# NRF24-SHIM.net
KiCad netlist of a schematic drawn in EAGLE
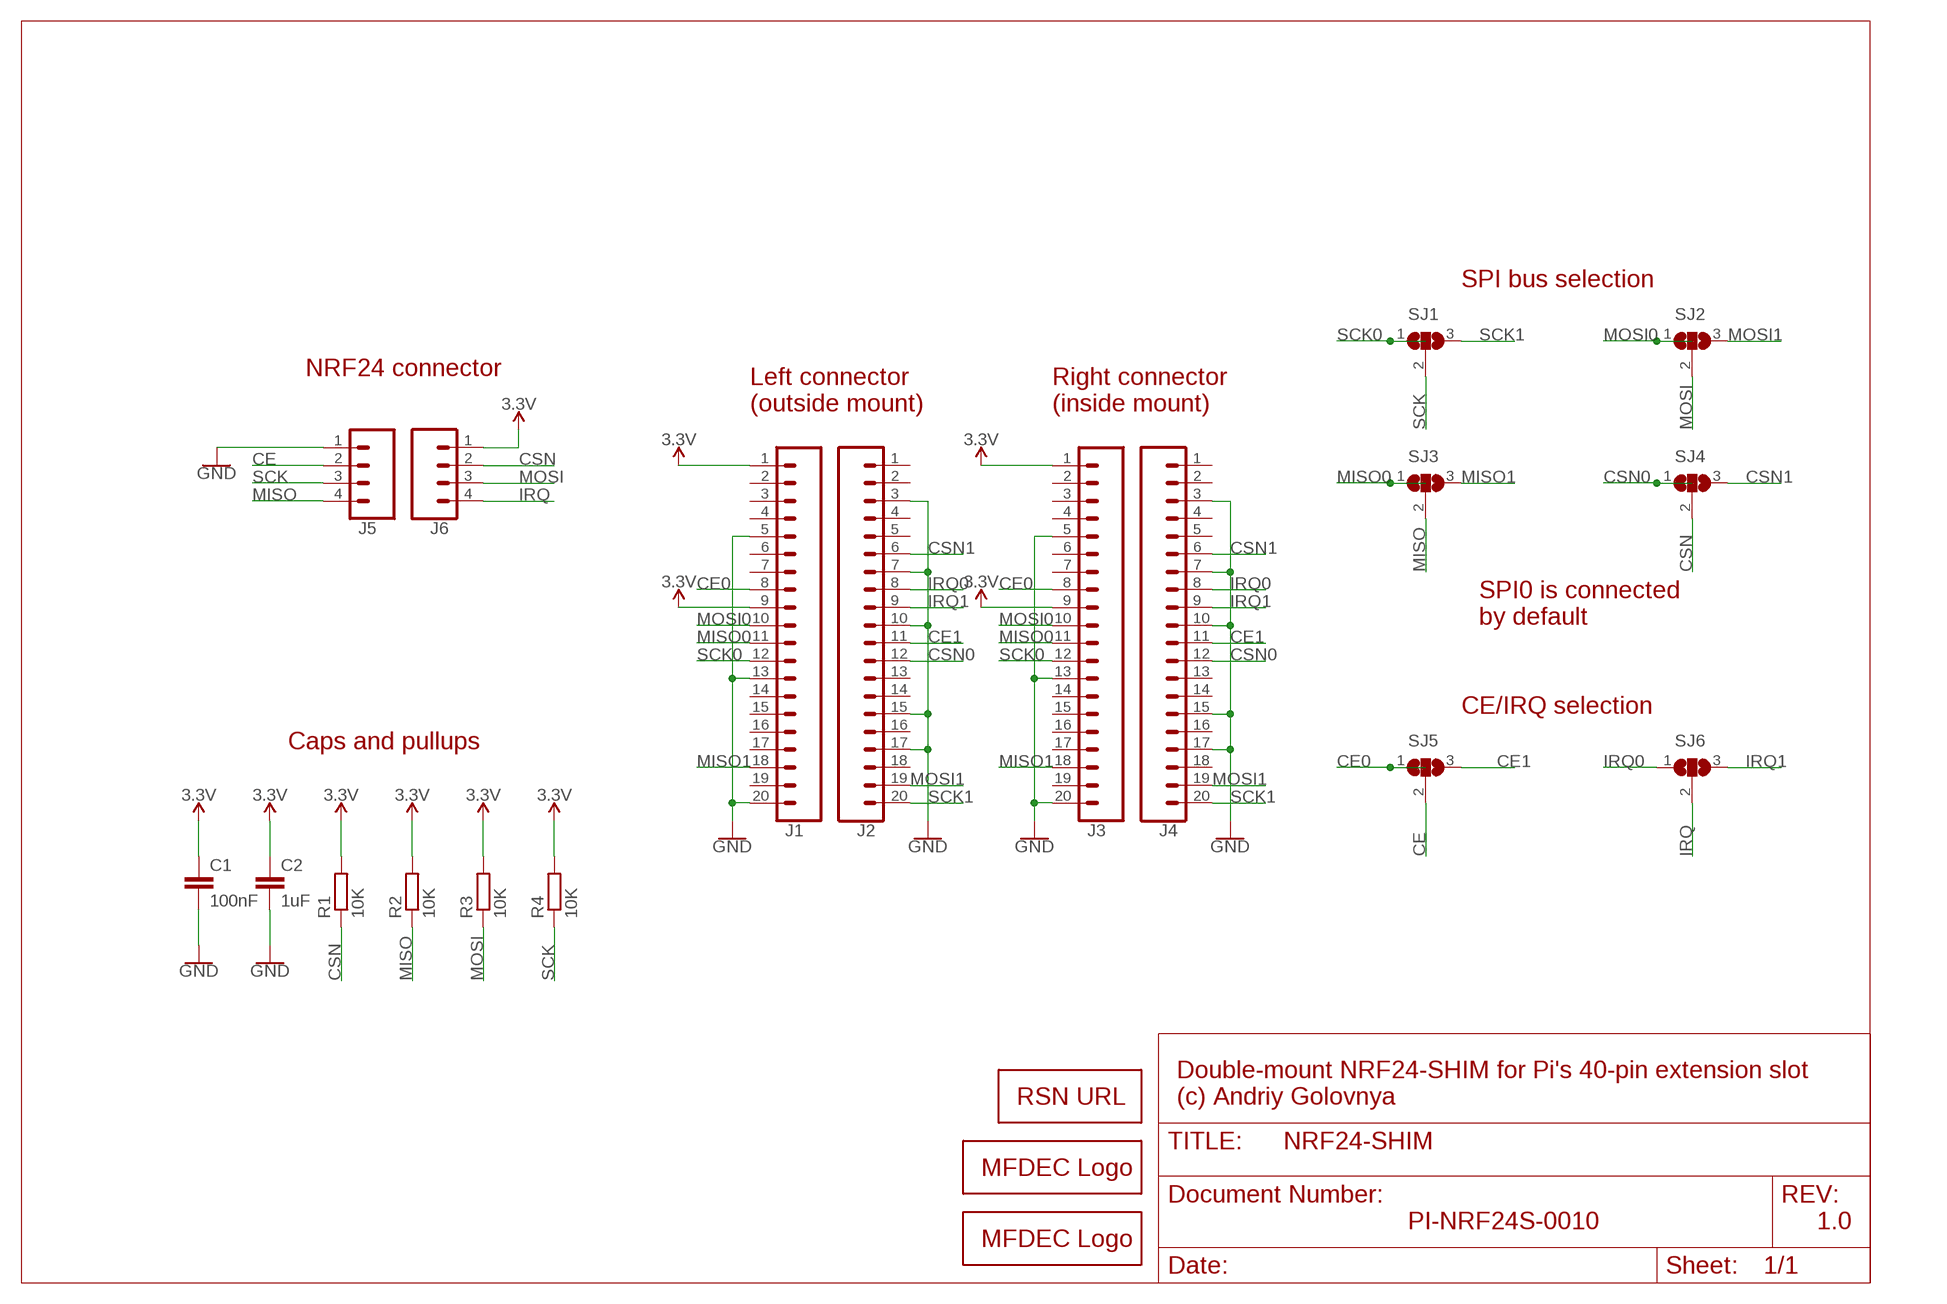
[diagram p0: schematic, sheet 1]

(export (version "E")
  (design (tool "Eeschema 10.0.6"))
  (components
    (comp (ref "C1")
      (value "100nF")
      (footprint "eagle-import:C0402")
      (libsource (lib "eagle-import") (part "C-EUC0402"))
    )
    (comp (ref "C2")
      (value "1uF")
      (footprint "eagle-import:C0603")
      (libsource (lib "eagle-import") (part "C-EUC0603"))
    )
    (comp (ref "J1")
      (value "CONN_20LOCK")
      (footprint "eagle-import:1X20_LOCK")
      (libsource (lib "eagle-import") (part "CONN_20LOCK"))
    )
    (comp (ref "J2")
      (value "CONN_20LOCK")
      (footprint "eagle-import:1X20_LOCK")
      (libsource (lib "eagle-import") (part "CONN_20LOCK"))
    )
    (comp (ref "J3")
      (value "CONN_20LOCK")
      (footprint "eagle-import:1X20_LOCK")
      (libsource (lib "eagle-import") (part "CONN_20LOCK"))
    )
    (comp (ref "J4")
      (value "CONN_20LOCK")
      (footprint "eagle-import:1X20_LOCK")
      (libsource (lib "eagle-import") (part "CONN_20LOCK"))
    )
    (comp (ref "J5")
      (value "CONN_04LOCK")
      (footprint "eagle-import:1X04_LOCK")
      (libsource (lib "eagle-import") (part "CONN_04LOCK"))
    )
    (comp (ref "J6")
      (value "CONN_04LOCK")
      (footprint "eagle-import:1X04_LOCK")
      (libsource (lib "eagle-import") (part "CONN_04LOCK"))
    )
    (comp (ref "LOGO1")
      (value "MFDECLOGO_SQ_8MM")
      (footprint "eagle-import:MFDEC_SQ_8MM")
      (libsource (lib "eagle-import") (part "MFDECLOGO_SQ_8MM"))
    )
    (comp (ref "LOGO2")
      (value "MFDECLOGO_L_20MM")
      (footprint "eagle-import:MFDEC_L_20MM")
      (libsource (lib "eagle-import") (part "MFDECLOGO_L_20MM"))
    )
    (comp (ref "LOGO3")
      (value "RSNURL_QR_10MM")
      (footprint "eagle-import:RSNURL_QR_10MM")
      (libsource (lib "eagle-import") (part "RSNURL_QR_10MM"))
    )
    (comp (ref "R1")
      (value "10K")
      (footprint "eagle-import:R0402")
      (libsource (lib "eagle-import") (part "R-EU_R0402"))
    )
    (comp (ref "R2")
      (value "10K")
      (footprint "eagle-import:R0402")
      (libsource (lib "eagle-import") (part "R-EU_R0402"))
    )
    (comp (ref "R3")
      (value "10K")
      (footprint "eagle-import:R0402")
      (libsource (lib "eagle-import") (part "R-EU_R0402"))
    )
    (comp (ref "R4")
      (value "10K")
      (footprint "eagle-import:R0402")
      (libsource (lib "eagle-import") (part "R-EU_R0402"))
    )
    (comp (ref "SJ1")
      (value "SJ2")
      (footprint "eagle-import:SJ_2")
      (libsource (lib "eagle-import") (part "SJ2"))
    )
    (comp (ref "SJ2")
      (value "SJ2")
      (footprint "eagle-import:SJ_2")
      (libsource (lib "eagle-import") (part "SJ2"))
    )
    (comp (ref "SJ3")
      (value "SJ2")
      (footprint "eagle-import:SJ_2")
      (libsource (lib "eagle-import") (part "SJ2"))
    )
    (comp (ref "SJ4")
      (value "SJ2")
      (footprint "eagle-import:SJ_2")
      (libsource (lib "eagle-import") (part "SJ2"))
    )
    (comp (ref "SJ5")
      (value "SJ2")
      (footprint "eagle-import:SJ_2")
      (libsource (lib "eagle-import") (part "SJ2"))
    )
    (comp (ref "SJ6")
      (value "SJ2")
      (footprint "eagle-import:SJ_2")
      (libsource (lib "eagle-import") (part "SJ2"))
    )
  )
  (nets
    (net (code "1") (name "/CE") (class "Default")
      (node (ref "J5") (pin "2") (pinfunction "2_2") (pintype "passive"))
      (node (ref "SJ5") (pin "2") (pinfunction "2_2") (pintype "passive"))
    )
    (net (code "2") (name "/CE0") (class "Default")
      (node (ref "J1") (pin "8") (pinfunction "8_8") (pintype "passive"))
      (node (ref "J3") (pin "8") (pinfunction "8_8") (pintype "passive"))
      (node (ref "SJ5") (pin "1") (pinfunction "1_1") (pintype "passive"))
    )
    (net (code "3") (name "/CE1") (class "Default")
      (node (ref "J2") (pin "11") (pinfunction "11_11") (pintype "passive"))
      (node (ref "J4") (pin "11") (pinfunction "11_11") (pintype "passive"))
      (node (ref "SJ5") (pin "3") (pinfunction "3_3") (pintype "passive"))
    )
    (net (code "4") (name "/CSN") (class "Default")
      (node (ref "J6") (pin "2") (pinfunction "2_2") (pintype "passive"))
      (node (ref "R1") (pin "1") (pinfunction "1_1") (pintype "passive"))
      (node (ref "SJ4") (pin "2") (pinfunction "2_2") (pintype "passive"))
    )
    (net (code "5") (name "/CSN0") (class "Default")
      (node (ref "J2") (pin "12") (pinfunction "12_12") (pintype "passive"))
      (node (ref "J4") (pin "12") (pinfunction "12_12") (pintype "passive"))
      (node (ref "SJ4") (pin "1") (pinfunction "1_1") (pintype "passive"))
    )
    (net (code "6") (name "/CSN1") (class "Default")
      (node (ref "J2") (pin "6") (pinfunction "6_6") (pintype "passive"))
      (node (ref "J4") (pin "6") (pinfunction "6_6") (pintype "passive"))
      (node (ref "SJ4") (pin "3") (pinfunction "3_3") (pintype "passive"))
    )
    (net (code "7") (name "/IRQ") (class "Default")
      (node (ref "J6") (pin "4") (pinfunction "4_4") (pintype "passive"))
      (node (ref "SJ6") (pin "2") (pinfunction "2_2") (pintype "passive"))
    )
    (net (code "8") (name "/IRQ0") (class "Default")
      (node (ref "J2") (pin "8") (pinfunction "8_8") (pintype "passive"))
      (node (ref "J4") (pin "8") (pinfunction "8_8") (pintype "passive"))
      (node (ref "SJ6") (pin "1") (pinfunction "1_1") (pintype "passive"))
    )
    (net (code "9") (name "/IRQ1") (class "Default")
      (node (ref "J2") (pin "9") (pinfunction "9_9") (pintype "passive"))
      (node (ref "J4") (pin "9") (pinfunction "9_9") (pintype "passive"))
      (node (ref "SJ6") (pin "3") (pinfunction "3_3") (pintype "passive"))
    )
    (net (code "10") (name "/MISO") (class "Default")
      (node (ref "J5") (pin "4") (pinfunction "4_4") (pintype "passive"))
      (node (ref "R2") (pin "1") (pinfunction "1_1") (pintype "passive"))
      (node (ref "SJ3") (pin "2") (pinfunction "2_2") (pintype "passive"))
    )
    (net (code "11") (name "/MISO0") (class "Default")
      (node (ref "J1") (pin "11") (pinfunction "11_11") (pintype "passive"))
      (node (ref "J3") (pin "11") (pinfunction "11_11") (pintype "passive"))
      (node (ref "SJ3") (pin "1") (pinfunction "1_1") (pintype "passive"))
    )
    (net (code "12") (name "/MISO1") (class "Default")
      (node (ref "J1") (pin "18") (pinfunction "18_18") (pintype "passive"))
      (node (ref "J3") (pin "18") (pinfunction "18_18") (pintype "passive"))
      (node (ref "SJ3") (pin "3") (pinfunction "3_3") (pintype "passive"))
    )
    (net (code "13") (name "/MOSI") (class "Default")
      (node (ref "J6") (pin "3") (pinfunction "3_3") (pintype "passive"))
      (node (ref "R3") (pin "1") (pinfunction "1_1") (pintype "passive"))
      (node (ref "SJ2") (pin "2") (pinfunction "2_2") (pintype "passive"))
    )
    (net (code "14") (name "/MOSI0") (class "Default")
      (node (ref "J1") (pin "10") (pinfunction "10_10") (pintype "passive"))
      (node (ref "J3") (pin "10") (pinfunction "10_10") (pintype "passive"))
      (node (ref "SJ2") (pin "1") (pinfunction "1_1") (pintype "passive"))
    )
    (net (code "15") (name "/MOSI1") (class "Default")
      (node (ref "J2") (pin "19") (pinfunction "19_19") (pintype "passive"))
      (node (ref "J4") (pin "19") (pinfunction "19_19") (pintype "passive"))
      (node (ref "SJ2") (pin "3") (pinfunction "3_3") (pintype "passive"))
    )
    (net (code "16") (name "/SCK") (class "Default")
      (node (ref "J5") (pin "3") (pinfunction "3_3") (pintype "passive"))
      (node (ref "R4") (pin "1") (pinfunction "1_1") (pintype "passive"))
      (node (ref "SJ1") (pin "2") (pinfunction "2_2") (pintype "passive"))
    )
    (net (code "17") (name "/SCK0") (class "Default")
      (node (ref "J1") (pin "12") (pinfunction "12_12") (pintype "passive"))
      (node (ref "J3") (pin "12") (pinfunction "12_12") (pintype "passive"))
      (node (ref "SJ1") (pin "1") (pinfunction "1_1") (pintype "passive"))
    )
    (net (code "18") (name "/SCK1") (class "Default")
      (node (ref "J2") (pin "20") (pinfunction "20_20") (pintype "passive"))
      (node (ref "J4") (pin "20") (pinfunction "20_20") (pintype "passive"))
      (node (ref "SJ1") (pin "3") (pinfunction "3_3") (pintype "passive"))
    )
    (net (code "19") (name "3.3V") (class "Default")
      (node (ref "C1") (pin "1") (pinfunction "1_1") (pintype "passive"))
      (node (ref "C2") (pin "1") (pinfunction "1_1") (pintype "passive"))
      (node (ref "J1") (pin "1") (pinfunction "1_1") (pintype "passive"))
      (node (ref "J1") (pin "9") (pinfunction "9_9") (pintype "passive"))
      (node (ref "J3") (pin "1") (pinfunction "1_1") (pintype "passive"))
      (node (ref "J3") (pin "9") (pinfunction "9_9") (pintype "passive"))
      (node (ref "J6") (pin "1") (pinfunction "1_1") (pintype "passive"))
      (node (ref "R1") (pin "2") (pinfunction "2_2") (pintype "passive"))
      (node (ref "R2") (pin "2") (pinfunction "2_2") (pintype "passive"))
      (node (ref "R3") (pin "2") (pinfunction "2_2") (pintype "passive"))
      (node (ref "R4") (pin "2") (pinfunction "2_2") (pintype "passive"))
    )
    (net (code "20") (name "GND") (class "Default")
      (node (ref "C1") (pin "2") (pinfunction "2_2") (pintype "passive"))
      (node (ref "C2") (pin "2") (pinfunction "2_2") (pintype "passive"))
      (node (ref "J1") (pin "13") (pinfunction "13_13") (pintype "passive"))
      (node (ref "J1") (pin "20") (pinfunction "20_20") (pintype "passive"))
      (node (ref "J1") (pin "5") (pinfunction "5_5") (pintype "passive"))
      (node (ref "J2") (pin "10") (pinfunction "10_10") (pintype "passive"))
      (node (ref "J2") (pin "15") (pinfunction "15_15") (pintype "passive"))
      (node (ref "J2") (pin "17") (pinfunction "17_17") (pintype "passive"))
      (node (ref "J2") (pin "3") (pinfunction "3_3") (pintype "passive"))
      (node (ref "J2") (pin "7") (pinfunction "7_7") (pintype "passive"))
      (node (ref "J3") (pin "13") (pinfunction "13_13") (pintype "passive"))
      (node (ref "J3") (pin "20") (pinfunction "20_20") (pintype "passive"))
      (node (ref "J3") (pin "5") (pinfunction "5_5") (pintype "passive"))
      (node (ref "J4") (pin "10") (pinfunction "10_10") (pintype "passive"))
      (node (ref "J4") (pin "15") (pinfunction "15_15") (pintype "passive"))
      (node (ref "J4") (pin "17") (pinfunction "17_17") (pintype "passive"))
      (node (ref "J4") (pin "3") (pinfunction "3_3") (pintype "passive"))
      (node (ref "J4") (pin "7") (pinfunction "7_7") (pintype "passive"))
      (node (ref "J5") (pin "1") (pinfunction "1_1") (pintype "passive"))
    )
    (net (code "21") (name "unconnected-(J1-Pad2)") (class "Default")
      (node (ref "J1") (pin "2") (pinfunction "2_2") (pintype "passive"))
    )
    (net (code "22") (name "unconnected-(J1-Pad3)") (class "Default")
      (node (ref "J1") (pin "3") (pinfunction "3_3") (pintype "passive"))
    )
    (net (code "23") (name "unconnected-(J1-Pad4)") (class "Default")
      (node (ref "J1") (pin "4") (pinfunction "4_4") (pintype "passive"))
    )
    (net (code "24") (name "unconnected-(J1-Pad6)") (class "Default")
      (node (ref "J1") (pin "6") (pinfunction "6_6") (pintype "passive"))
    )
    (net (code "25") (name "unconnected-(J1-Pad7)") (class "Default")
      (node (ref "J1") (pin "7") (pinfunction "7_7") (pintype "passive"))
    )
    (net (code "26") (name "unconnected-(J1-Pad14)") (class "Default")
      (node (ref "J1") (pin "14") (pinfunction "14_14") (pintype "passive"))
    )
    (net (code "27") (name "unconnected-(J1-Pad15)") (class "Default")
      (node (ref "J1") (pin "15") (pinfunction "15_15") (pintype "passive"))
    )
    (net (code "28") (name "unconnected-(J1-Pad16)") (class "Default")
      (node (ref "J1") (pin "16") (pinfunction "16_16") (pintype "passive"))
    )
    (net (code "29") (name "unconnected-(J1-Pad17)") (class "Default")
      (node (ref "J1") (pin "17") (pinfunction "17_17") (pintype "passive"))
    )
    (net (code "30") (name "unconnected-(J1-Pad19)") (class "Default")
      (node (ref "J1") (pin "19") (pinfunction "19_19") (pintype "passive"))
    )
    (net (code "31") (name "unconnected-(J2-Pad1)") (class "Default")
      (node (ref "J2") (pin "1") (pinfunction "1_1") (pintype "passive"))
    )
    (net (code "32") (name "unconnected-(J2-Pad2)") (class "Default")
      (node (ref "J2") (pin "2") (pinfunction "2_2") (pintype "passive"))
    )
    (net (code "33") (name "unconnected-(J2-Pad4)") (class "Default")
      (node (ref "J2") (pin "4") (pinfunction "4_4") (pintype "passive"))
    )
    (net (code "34") (name "unconnected-(J2-Pad5)") (class "Default")
      (node (ref "J2") (pin "5") (pinfunction "5_5") (pintype "passive"))
    )
    (net (code "35") (name "unconnected-(J2-Pad13)") (class "Default")
      (node (ref "J2") (pin "13") (pinfunction "13_13") (pintype "passive"))
    )
    (net (code "36") (name "unconnected-(J2-Pad14)") (class "Default")
      (node (ref "J2") (pin "14") (pinfunction "14_14") (pintype "passive"))
    )
    (net (code "37") (name "unconnected-(J2-Pad16)") (class "Default")
      (node (ref "J2") (pin "16") (pinfunction "16_16") (pintype "passive"))
    )
    (net (code "38") (name "unconnected-(J2-Pad18)") (class "Default")
      (node (ref "J2") (pin "18") (pinfunction "18_18") (pintype "passive"))
    )
    (net (code "39") (name "unconnected-(J3-Pad2)") (class "Default")
      (node (ref "J3") (pin "2") (pinfunction "2_2") (pintype "passive"))
    )
    (net (code "40") (name "unconnected-(J3-Pad3)") (class "Default")
      (node (ref "J3") (pin "3") (pinfunction "3_3") (pintype "passive"))
    )
    (net (code "41") (name "unconnected-(J3-Pad4)") (class "Default")
      (node (ref "J3") (pin "4") (pinfunction "4_4") (pintype "passive"))
    )
    (net (code "42") (name "unconnected-(J3-Pad6)") (class "Default")
      (node (ref "J3") (pin "6") (pinfunction "6_6") (pintype "passive"))
    )
    (net (code "43") (name "unconnected-(J3-Pad7)") (class "Default")
      (node (ref "J3") (pin "7") (pinfunction "7_7") (pintype "passive"))
    )
    (net (code "44") (name "unconnected-(J3-Pad14)") (class "Default")
      (node (ref "J3") (pin "14") (pinfunction "14_14") (pintype "passive"))
    )
    (net (code "45") (name "unconnected-(J3-Pad15)") (class "Default")
      (node (ref "J3") (pin "15") (pinfunction "15_15") (pintype "passive"))
    )
    (net (code "46") (name "unconnected-(J3-Pad16)") (class "Default")
      (node (ref "J3") (pin "16") (pinfunction "16_16") (pintype "passive"))
    )
    (net (code "47") (name "unconnected-(J3-Pad17)") (class "Default")
      (node (ref "J3") (pin "17") (pinfunction "17_17") (pintype "passive"))
    )
    (net (code "48") (name "unconnected-(J3-Pad19)") (class "Default")
      (node (ref "J3") (pin "19") (pinfunction "19_19") (pintype "passive"))
    )
    (net (code "49") (name "unconnected-(J4-Pad1)") (class "Default")
      (node (ref "J4") (pin "1") (pinfunction "1_1") (pintype "passive"))
    )
    (net (code "50") (name "unconnected-(J4-Pad2)") (class "Default")
      (node (ref "J4") (pin "2") (pinfunction "2_2") (pintype "passive"))
    )
    (net (code "51") (name "unconnected-(J4-Pad4)") (class "Default")
      (node (ref "J4") (pin "4") (pinfunction "4_4") (pintype "passive"))
    )
    (net (code "52") (name "unconnected-(J4-Pad5)") (class "Default")
      (node (ref "J4") (pin "5") (pinfunction "5_5") (pintype "passive"))
    )
    (net (code "53") (name "unconnected-(J4-Pad13)") (class "Default")
      (node (ref "J4") (pin "13") (pinfunction "13_13") (pintype "passive"))
    )
    (net (code "54") (name "unconnected-(J4-Pad14)") (class "Default")
      (node (ref "J4") (pin "14") (pinfunction "14_14") (pintype "passive"))
    )
    (net (code "55") (name "unconnected-(J4-Pad16)") (class "Default")
      (node (ref "J4") (pin "16") (pinfunction "16_16") (pintype "passive"))
    )
    (net (code "56") (name "unconnected-(J4-Pad18)") (class "Default")
      (node (ref "J4") (pin "18") (pinfunction "18_18") (pintype "passive"))
    )
  )
)
